# mugsy-cone-mech-pcb-schematic-eagle.net
KiCad netlist of a schematic drawn in EAGLE
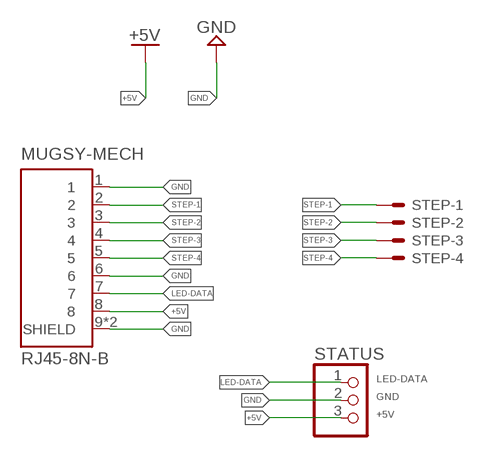
[diagram p0: schematic, sheet 1]

(export (version "E")
  (design (tool "Eeschema 10.0.6"))
  (components
    (comp (ref "MUGSY-MECH")
      (value "RJ45-8N-B")
      (footprint "eagle-import:TE_RJ45-8N-B")
      (fields (field (name "MF") "TE Connectivity"))
      (libsource (lib "eagle-import") (part "RJ45-8N-B"))
    )
    (comp (ref "STATUS")
      (value "PINHD-1X3CB")
      (footprint "eagle-import:1X03-CLEANBIG")
      (libsource (lib "eagle-import") (part "PINHD-1X3CB"))
    )
    (comp (ref "STEP")
      (value "JST-XH-04-PIN-ROUND-PAD")
      (footprint "eagle-import:JST-XH-04-PACKAGE-ROUND-PAD")
      (libsource (lib "eagle-import") (part "JST-XH-04-PIN-ROUND-PAD"))
    )
  )
  (nets
    (net (code "1") (name "+5V") (class "Default")
      (node (ref "MUGSY-MECH") (pin "8") (pinfunction "8_8") (pintype "passive"))
      (node (ref "STATUS") (pin "3") (pinfunction "3_3") (pintype "passive"))
    )
    (net (code "2") (name "GND") (class "Default")
      (node (ref "MUGSY-MECH") (pin "1") (pinfunction "1_1") (pintype "passive"))
      (node (ref "MUGSY-MECH") (pin "10") (pinfunction "SHIELD_10") (pintype "passive"))
      (node (ref "MUGSY-MECH") (pin "6") (pinfunction "6_6") (pintype "passive"))
      (node (ref "MUGSY-MECH") (pin "9") (pinfunction "SHIELD_9") (pintype "passive"))
      (node (ref "STATUS") (pin "2") (pinfunction "2_2") (pintype "passive"))
    )
    (net (code "3") (name "LED-DATA") (class "Default")
      (node (ref "MUGSY-MECH") (pin "7") (pinfunction "7_7") (pintype "passive"))
      (node (ref "STATUS") (pin "1") (pinfunction "1_1") (pintype "passive"))
    )
    (net (code "4") (name "STEP-1") (class "Default")
      (node (ref "MUGSY-MECH") (pin "2") (pinfunction "2_2") (pintype "passive"))
      (node (ref "STEP") (pin "1") (pinfunction "S_1") (pintype "passive"))
    )
    (net (code "5") (name "STEP-2") (class "Default")
      (node (ref "MUGSY-MECH") (pin "3") (pinfunction "3_3") (pintype "passive"))
      (node (ref "STEP") (pin "2") (pinfunction "S_2") (pintype "passive"))
    )
    (net (code "6") (name "STEP-3") (class "Default")
      (node (ref "MUGSY-MECH") (pin "4") (pinfunction "4_4") (pintype "passive"))
      (node (ref "STEP") (pin "3") (pinfunction "S_3") (pintype "passive"))
    )
    (net (code "7") (name "STEP-4") (class "Default")
      (node (ref "MUGSY-MECH") (pin "5") (pinfunction "5_5") (pintype "passive"))
      (node (ref "STEP") (pin "4") (pinfunction "S_4") (pintype "passive"))
    )
  )
)
